# SCH_Landing_Gear_Panel_v2_2021-07-29.net
KiCad netlist of a schematic drawn in EasyEDA
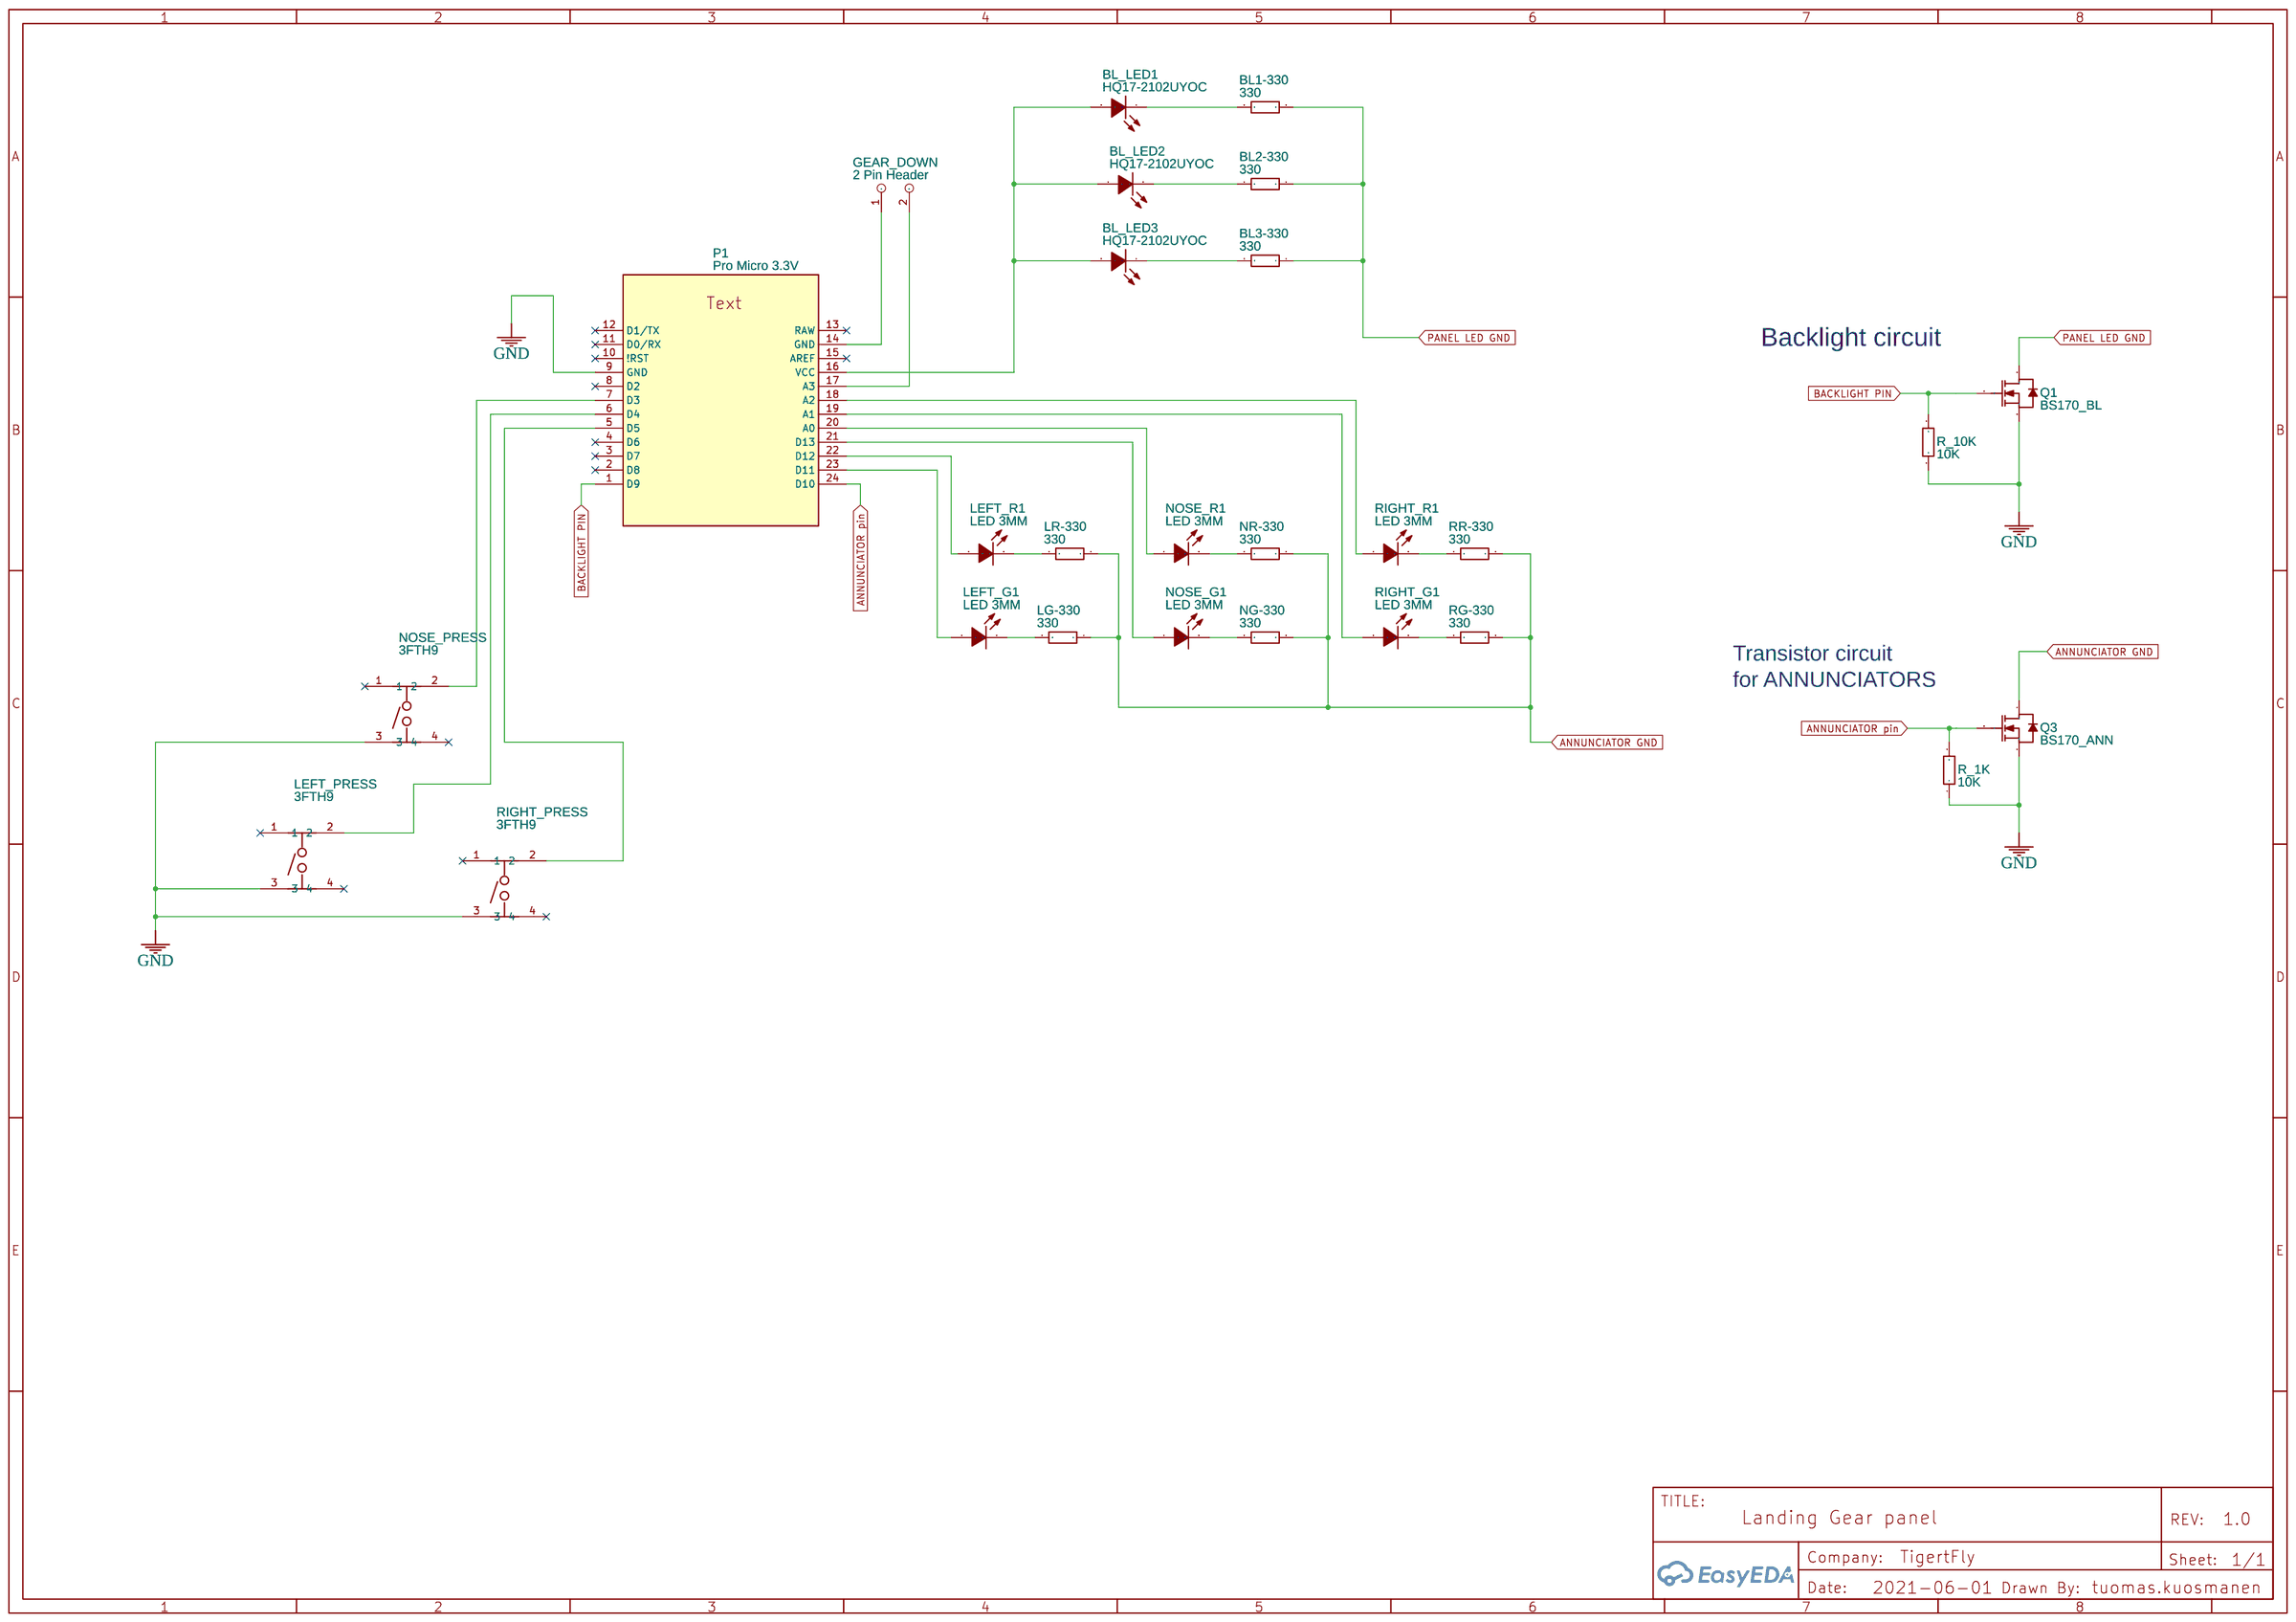
[diagram p0: schematic sheet]

(export (version "E")
  (design (tool "Eeschema 10.0.6"))
  (components
    (comp (ref "BL1-330")
      (value "330")
      (fields
        (field (name "BOM_Manufacturer Part") "1206W4J0331T5E")
        (field (name "BOM_Supplier Part") "C25374")
      )
      (libsource (lib "") (part "1206W4J0331T5E_5"))
    )
    (comp (ref "BL2-330")
      (value "330")
      (fields
        (field (name "BOM_Manufacturer Part") "1206W4J0331T5E")
        (field (name "BOM_Supplier Part") "C25374")
      )
      (libsource (lib "") (part "1206W4J0331T5E_8"))
    )
    (comp (ref "BL3-330")
      (value "330")
      (fields
        (field (name "BOM_Manufacturer Part") "1206W4J0331T5E")
        (field (name "BOM_Supplier Part") "C25374")
      )
      (libsource (lib "") (part "1206W4J0331T5E_1"))
    )
    (comp (ref "BL_LED1")
      (value "HQ17-2102UYOC")
      (fields (field (name "BOM_Supplier Part") "C154481"))
      (libsource (lib "") (part "HQ17-2102UYOC"))
    )
    (comp (ref "BL_LED2")
      (value "HQ17-2102UYOC")
      (fields (field (name "BOM_Supplier Part") "C154481"))
      (libsource (lib "") (part "HQ17-2102UYOC"))
    )
    (comp (ref "BL_LED3")
      (value "HQ17-2102UYOC")
      (fields (field (name "BOM_Supplier Part") "C154481"))
      (libsource (lib "") (part "HQ17-2102UYOC"))
    )
    (comp (ref "GEAR_DOWN") (value "2 Pin Header") (libsource (lib "") (part "2 Pin Header")))
    (comp (ref "LEFT_G1")
      (value "LED 3MM")
      (fields (field (name "BOM_Supplier Part") "C62095"))
      (libsource (lib "") (part "LED 3MM"))
    )
    (comp (ref "LEFT_PRESS")
      (value "3FTH9")
      (fields (field (name "BOM_Supplier Part") "679-3730-5-ND"))
      (libsource (lib "") (part "3FTH9_2"))
    )
    (comp (ref "LEFT_R1")
      (value "LED 3MM")
      (fields (field (name "BOM_Supplier Part") "C62095"))
      (libsource (lib "") (part "LED 3MM_2"))
    )
    (comp (ref "LG-330")
      (value "330")
      (fields
        (field (name "BOM_Manufacturer Part") "1206W4J0331T5E")
        (field (name "BOM_Supplier Part") "C25374")
      )
      (libsource (lib "") (part "1206W4J0331T5E_3"))
    )
    (comp (ref "LR-330")
      (value "330")
      (fields
        (field (name "BOM_Manufacturer Part") "1206W4J0331T5E")
        (field (name "BOM_Supplier Part") "C25374")
      )
      (libsource (lib "") (part "1206W4J0331T5E"))
    )
    (comp (ref "NG-330")
      (value "330")
      (fields
        (field (name "BOM_Manufacturer Part") "1206W4J0331T5E")
        (field (name "BOM_Supplier Part") "C25374")
      )
      (libsource (lib "") (part "1206W4J0331T5E_2"))
    )
    (comp (ref "NOSE_G1")
      (value "LED 3MM")
      (fields (field (name "BOM_Supplier Part") "C62095"))
      (libsource (lib "") (part "LED 3MM_5"))
    )
    (comp (ref "NOSE_PRESS")
      (value "3FTH9")
      (fields (field (name "BOM_Supplier Part") "679-3730-5-ND"))
      (libsource (lib "") (part "3FTH9_1"))
    )
    (comp (ref "NOSE_R1")
      (value "LED 3MM")
      (fields (field (name "BOM_Supplier Part") "C62095"))
      (libsource (lib "") (part "LED 3MM_1"))
    )
    (comp (ref "NR-330")
      (value "330")
      (fields
        (field (name "BOM_Manufacturer Part") "1206W4J0331T5E")
        (field (name "BOM_Supplier Part") "C25374")
      )
      (libsource (lib "") (part "1206W4J0331T5E_6"))
    )
    (comp (ref "P1")
      (value "Pro Micro 3.3V")
      (fields (field (name "BOM_Supplier Part") "12587"))
      (libsource (lib "") (part "Pro Micro 3.3V"))
    )
    (comp (ref "Q1")
      (value "BS170_BL")
      (fields (field (name "BOM_Manufacturer Part") "BS170") (field (name "BOM_Supplier Part") "C111691"))
      (libsource (lib "") (part "BS170"))
    )
    (comp (ref "Q3")
      (value "BS170_ANN")
      (fields (field (name "BOM_Manufacturer Part") "BS170") (field (name "BOM_Supplier Part") "C111691"))
      (libsource (lib "") (part "BS170"))
    )
    (comp (ref "RG-330")
      (value "330")
      (fields
        (field (name "BOM_Manufacturer Part") "1206W4J0331T5E")
        (field (name "BOM_Supplier Part") "C25374")
      )
      (libsource (lib "") (part "1206W4J0331T5E_7"))
    )
    (comp (ref "RIGHT_G1")
      (value "LED 3MM")
      (fields (field (name "BOM_Supplier Part") "C62095"))
      (libsource (lib "") (part "LED 3MM_4"))
    )
    (comp (ref "RIGHT_PRESS")
      (value "3FTH9")
      (fields (field (name "BOM_Supplier Part") "679-3730-5-ND"))
      (libsource (lib "") (part "3FTH9"))
    )
    (comp (ref "RIGHT_R1")
      (value "LED 3MM")
      (fields (field (name "BOM_Supplier Part") "C62095"))
      (libsource (lib "") (part "LED 3MM_3"))
    )
    (comp (ref "RR-330")
      (value "330")
      (fields
        (field (name "BOM_Manufacturer Part") "1206W4J0331T5E")
        (field (name "BOM_Supplier Part") "C25374")
      )
      (libsource (lib "") (part "1206W4J0331T5E_9"))
    )
    (comp (ref "R_1K")
      (value "10K")
      (fields
        (field (name "BOM_Manufacturer Part") "1206W4J0331T5E")
        (field (name "BOM_Supplier Part") "C25374")
      )
      (libsource (lib "") (part "1206W4J0331T5E_10"))
    )
    (comp (ref "R_10K")
      (value "10K")
      (fields
        (field (name "BOM_Manufacturer Part") "1206W4J0331T5E")
        (field (name "BOM_Supplier Part") "C25374")
      )
      (libsource (lib "") (part "1206W4J0331T5E_4"))
    )
  )
  (nets
    (net (code "1") (name "ANNUNCIATOR GND") (class "Default")
      (node (ref "LG-330") (pin "1") (pinfunction "1_1") (pintype "input"))
      (node (ref "LR-330") (pin "1") (pinfunction "1_1") (pintype "input"))
      (node (ref "NG-330") (pin "1") (pinfunction "1_1") (pintype "input"))
      (node (ref "NR-330") (pin "1") (pinfunction "1_1") (pintype "input"))
      (node (ref "Q3") (pin "1") (pinfunction "D_1") (pintype "unspecified"))
      (node (ref "RG-330") (pin "1") (pinfunction "1_1") (pintype "input"))
      (node (ref "RR-330") (pin "1") (pinfunction "1_1") (pintype "input"))
    )
    (net (code "2") (name "ANNUNCIATOR pin") (class "Default")
      (node (ref "P1") (pin "24") (pinfunction "D10_24") (pintype "unspecified"))
      (node (ref "Q3") (pin "2") (pinfunction "G_2") (pintype "unspecified"))
      (node (ref "R_1K") (pin "2") (pinfunction "2_2") (pintype "input"))
    )
    (net (code "3") (name "BACKLIGHT PIN") (class "Default")
      (node (ref "P1") (pin "1") (pinfunction "D9_1") (pintype "unspecified"))
      (node (ref "Q1") (pin "2") (pinfunction "G_2") (pintype "unspecified"))
      (node (ref "R_10K") (pin "2") (pinfunction "2_2") (pintype "input"))
    )
    (net (code "4") (name "GND") (class "Default")
      (node (ref "LEFT_PRESS") (pin "3") (pinfunction "3_3") (pintype "unspecified"))
      (node (ref "NOSE_PRESS") (pin "3") (pinfunction "3_3") (pintype "unspecified"))
      (node (ref "P1") (pin "9") (pinfunction "GND_9") (pintype "unspecified"))
      (node (ref "Q1") (pin "3") (pinfunction "S_3") (pintype "unspecified"))
      (node (ref "Q3") (pin "3") (pinfunction "S_3") (pintype "unspecified"))
      (node (ref "RIGHT_PRESS") (pin "3") (pinfunction "3_3") (pintype "unspecified"))
      (node (ref "R_10K") (pin "1") (pinfunction "1_1") (pintype "input"))
      (node (ref "R_1K") (pin "1") (pinfunction "1_1") (pintype "input"))
    )
    (net (code "5") (name "Net-(BL_LED1-A)") (class "Default")
      (node (ref "BL_LED1") (pin "2") (pinfunction "A_2") (pintype "unspecified"))
      (node (ref "BL_LED2") (pin "2") (pinfunction "A_2") (pintype "unspecified"))
      (node (ref "BL_LED3") (pin "2") (pinfunction "A_2") (pintype "unspecified"))
      (node (ref "P1") (pin "16") (pinfunction "VCC_16") (pintype "unspecified"))
    )
    (net (code "6") (name "Net-(BL_LED1-K)") (class "Default")
      (node (ref "BL1-330") (pin "2") (pinfunction "2_2") (pintype "input"))
      (node (ref "BL_LED1") (pin "1") (pinfunction "K_1") (pintype "unspecified"))
    )
    (net (code "7") (name "Net-(BL_LED2-K)") (class "Default")
      (node (ref "BL2-330") (pin "2") (pinfunction "2_2") (pintype "input"))
      (node (ref "BL_LED2") (pin "1") (pinfunction "K_1") (pintype "unspecified"))
    )
    (net (code "8") (name "Net-(BL_LED3-K)") (class "Default")
      (node (ref "BL3-330") (pin "2") (pinfunction "2_2") (pintype "input"))
      (node (ref "BL_LED3") (pin "1") (pinfunction "K_1") (pintype "unspecified"))
    )
    (net (code "9") (name "Net-(GEAR_DOWN-Pad1)") (class "Default")
      (node (ref "GEAR_DOWN") (pin "1") (pinfunction "1_1") (pintype "unspecified"))
      (node (ref "P1") (pin "14") (pinfunction "GND_14") (pintype "unspecified"))
    )
    (net (code "10") (name "Net-(LEFT_G1-A)") (class "Default")
      (node (ref "LEFT_G1") (pin "1") (pinfunction "A_1") (pintype "unspecified"))
      (node (ref "P1") (pin "23") (pinfunction "D11_23") (pintype "unspecified"))
    )
    (net (code "11") (name "Net-(LEFT_G1-K)") (class "Default")
      (node (ref "LEFT_G1") (pin "2") (pinfunction "K_2") (pintype "unspecified"))
      (node (ref "LG-330") (pin "2") (pinfunction "2_2") (pintype "input"))
    )
    (net (code "12") (name "Net-(LEFT_R1-A)") (class "Default")
      (node (ref "LEFT_R1") (pin "1") (pinfunction "A_1") (pintype "unspecified"))
      (node (ref "P1") (pin "22") (pinfunction "D12_22") (pintype "unspecified"))
    )
    (net (code "13") (name "Net-(LEFT_R1-K)") (class "Default")
      (node (ref "LEFT_R1") (pin "2") (pinfunction "K_2") (pintype "unspecified"))
      (node (ref "LR-330") (pin "2") (pinfunction "2_2") (pintype "input"))
    )
    (net (code "14") (name "Net-(NOSE_G1-A)") (class "Default")
      (node (ref "NOSE_G1") (pin "1") (pinfunction "A_1") (pintype "unspecified"))
      (node (ref "P1") (pin "21") (pinfunction "D13_21") (pintype "unspecified"))
    )
    (net (code "15") (name "Net-(NOSE_G1-K)") (class "Default")
      (node (ref "NG-330") (pin "2") (pinfunction "2_2") (pintype "input"))
      (node (ref "NOSE_G1") (pin "2") (pinfunction "K_2") (pintype "unspecified"))
    )
    (net (code "16") (name "Net-(NOSE_R1-A)") (class "Default")
      (node (ref "NOSE_R1") (pin "1") (pinfunction "A_1") (pintype "unspecified"))
      (node (ref "P1") (pin "20") (pinfunction "A0_20") (pintype "unspecified"))
    )
    (net (code "17") (name "Net-(NOSE_R1-K)") (class "Default")
      (node (ref "NOSE_R1") (pin "2") (pinfunction "K_2") (pintype "unspecified"))
      (node (ref "NR-330") (pin "2") (pinfunction "2_2") (pintype "input"))
    )
    (net (code "18") (name "Net-(P1-A1)") (class "Default")
      (node (ref "P1") (pin "19") (pinfunction "A1_19") (pintype "unspecified"))
      (node (ref "RIGHT_G1") (pin "1") (pinfunction "A_1") (pintype "unspecified"))
    )
    (net (code "19") (name "Net-(P1-A2)") (class "Default")
      (node (ref "P1") (pin "18") (pinfunction "A2_18") (pintype "unspecified"))
      (node (ref "RIGHT_R1") (pin "1") (pinfunction "A_1") (pintype "unspecified"))
    )
    (net (code "20") (name "Net-(P1-A3)") (class "Default")
      (node (ref "GEAR_DOWN") (pin "2") (pinfunction "2_2") (pintype "unspecified"))
      (node (ref "P1") (pin "17") (pinfunction "A3_17") (pintype "unspecified"))
    )
    (net (code "21") (name "Net-(P1-D3)") (class "Default")
      (node (ref "NOSE_PRESS") (pin "2") (pinfunction "2_2") (pintype "unspecified"))
      (node (ref "P1") (pin "7") (pinfunction "D3_7") (pintype "unspecified"))
    )
    (net (code "22") (name "Net-(P1-D4)") (class "Default")
      (node (ref "LEFT_PRESS") (pin "2") (pinfunction "2_2") (pintype "unspecified"))
      (node (ref "P1") (pin "6") (pinfunction "D4_6") (pintype "unspecified"))
    )
    (net (code "23") (name "Net-(P1-D5)") (class "Default")
      (node (ref "P1") (pin "5") (pinfunction "D5_5") (pintype "unspecified"))
      (node (ref "RIGHT_PRESS") (pin "2") (pinfunction "2_2") (pintype "unspecified"))
    )
    (net (code "24") (name "Net-(RIGHT_G1-K)") (class "Default")
      (node (ref "RG-330") (pin "2") (pinfunction "2_2") (pintype "input"))
      (node (ref "RIGHT_G1") (pin "2") (pinfunction "K_2") (pintype "unspecified"))
    )
    (net (code "25") (name "Net-(RIGHT_R1-K)") (class "Default")
      (node (ref "RIGHT_R1") (pin "2") (pinfunction "K_2") (pintype "unspecified"))
      (node (ref "RR-330") (pin "2") (pinfunction "2_2") (pintype "input"))
    )
    (net (code "26") (name "PANEL LED GND") (class "Default")
      (node (ref "BL1-330") (pin "1") (pinfunction "1_1") (pintype "input"))
      (node (ref "BL2-330") (pin "1") (pinfunction "1_1") (pintype "input"))
      (node (ref "BL3-330") (pin "1") (pinfunction "1_1") (pintype "input"))
      (node (ref "Q1") (pin "1") (pinfunction "D_1") (pintype "unspecified"))
    )
    (net (code "27") (name "unconnected-(LEFT_PRESS-Pad1)") (class "Default")
      (node (ref "LEFT_PRESS") (pin "1") (pinfunction "1_1") (pintype "unspecified+no_connect"))
    )
    (net (code "28") (name "unconnected-(LEFT_PRESS-Pad4)") (class "Default")
      (node (ref "LEFT_PRESS") (pin "4") (pinfunction "4_4") (pintype "unspecified+no_connect"))
    )
    (net (code "29") (name "unconnected-(NOSE_PRESS-Pad1)") (class "Default")
      (node (ref "NOSE_PRESS") (pin "1") (pinfunction "1_1") (pintype "unspecified+no_connect"))
    )
    (net (code "30") (name "unconnected-(NOSE_PRESS-Pad4)") (class "Default")
      (node (ref "NOSE_PRESS") (pin "4") (pinfunction "4_4") (pintype "unspecified+no_connect"))
    )
    (net (code "31") (name "unconnected-(P1-!RST-Pad10)") (class "Default")
      (node (ref "P1") (pin "10") (pinfunction "!RST_10") (pintype "unspecified+no_connect"))
    )
    (net (code "32") (name "unconnected-(P1-AREF-Pad15)") (class "Default")
      (node (ref "P1") (pin "15") (pinfunction "AREF_15") (pintype "unspecified+no_connect"))
    )
    (net (code "33") (name "unconnected-(P1-D0{slash}RX-Pad11)") (class "Default")
      (node (ref "P1") (pin "11") (pinfunction "D0/RX_11") (pintype "unspecified+no_connect"))
    )
    (net (code "34") (name "unconnected-(P1-D1{slash}TX-Pad12)") (class "Default")
      (node (ref "P1") (pin "12") (pinfunction "D1/TX_12") (pintype "unspecified+no_connect"))
    )
    (net (code "35") (name "unconnected-(P1-D2-Pad8)") (class "Default")
      (node (ref "P1") (pin "8") (pinfunction "D2_8") (pintype "unspecified+no_connect"))
    )
    (net (code "36") (name "unconnected-(P1-D6-Pad4)") (class "Default")
      (node (ref "P1") (pin "4") (pinfunction "D6_4") (pintype "unspecified+no_connect"))
    )
    (net (code "37") (name "unconnected-(P1-D7-Pad3)") (class "Default")
      (node (ref "P1") (pin "3") (pinfunction "D7_3") (pintype "unspecified+no_connect"))
    )
    (net (code "38") (name "unconnected-(P1-D8-Pad2)") (class "Default")
      (node (ref "P1") (pin "2") (pinfunction "D8_2") (pintype "unspecified+no_connect"))
    )
    (net (code "39") (name "unconnected-(P1-RAW-Pad13)") (class "Default")
      (node (ref "P1") (pin "13") (pinfunction "RAW_13") (pintype "unspecified+no_connect"))
    )
    (net (code "40") (name "unconnected-(RIGHT_PRESS-Pad1)") (class "Default")
      (node (ref "RIGHT_PRESS") (pin "1") (pinfunction "1_1") (pintype "unspecified+no_connect"))
    )
    (net (code "41") (name "unconnected-(RIGHT_PRESS-Pad4)") (class "Default")
      (node (ref "RIGHT_PRESS") (pin "4") (pinfunction "4_4") (pintype "unspecified+no_connect"))
    )
  )
)
